# analog_pwr.net
KiCad netlist of a schematic drawn in Altium Designer
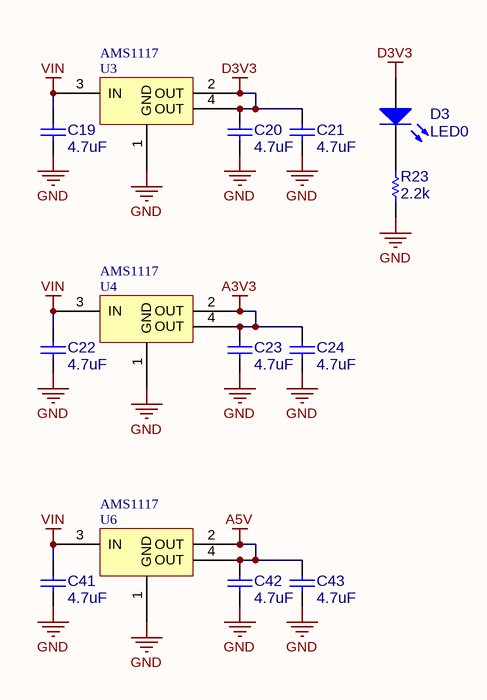
[diagram p0: analog_pwr.SchDoc]

(export (version "E")
  (design (tool "Eeschema 10.0.6"))
  (components
    (comp (ref "C19")
      (value "4.7uF")
      (footprint "TANT_B")
      (description "Capacitor")
      (fields (field (name "PUBLISHER") "Altium Limited"))
      (libsource (lib "Miscellaneous Devices") (part "Cap"))
    )
    (comp (ref "C20")
      (value "4.7uF")
      (footprint "C0603")
      (description "Capacitor")
      (fields (field (name "PUBLISHER") "Altium Limited"))
      (libsource (lib "Miscellaneous Devices") (part "Cap"))
    )
    (comp (ref "C21")
      (value "4.7uF")
      (footprint "TANT_B")
      (description "Capacitor")
      (fields (field (name "PUBLISHER") "Altium Limited"))
      (libsource (lib "Miscellaneous Devices") (part "Cap"))
    )
    (comp (ref "C22")
      (value "4.7uF")
      (footprint "TANT_B")
      (description "Capacitor")
      (fields (field (name "PUBLISHER") "Altium Limited"))
      (libsource (lib "Miscellaneous Devices") (part "Cap"))
    )
    (comp (ref "C23")
      (value "4.7uF")
      (footprint "C0603")
      (description "Capacitor")
      (fields (field (name "PUBLISHER") "Altium Limited"))
      (libsource (lib "Miscellaneous Devices") (part "Cap"))
    )
    (comp (ref "C24")
      (value "4.7uF")
      (footprint "TANT_B")
      (description "Capacitor")
      (fields (field (name "PUBLISHER") "Altium Limited"))
      (libsource (lib "Miscellaneous Devices") (part "Cap"))
    )
    (comp (ref "C41")
      (value "4.7uF")
      (footprint "TANT_B")
      (description "Capacitor")
      (fields (field (name "PUBLISHER") "Altium Limited"))
      (libsource (lib "Miscellaneous Devices") (part "Cap"))
    )
    (comp (ref "C42")
      (value "4.7uF")
      (footprint "C0603")
      (description "Capacitor")
      (fields (field (name "PUBLISHER") "Altium Limited"))
      (libsource (lib "Miscellaneous Devices") (part "Cap"))
    )
    (comp (ref "C43")
      (value "4.7uF")
      (footprint "TANT_B")
      (description "Capacitor")
      (fields (field (name "PUBLISHER") "Altium Limited"))
      (libsource (lib "Miscellaneous Devices") (part "Cap"))
    )
    (comp (ref "D3")
      (value "LED0")
      (footprint "LED0603")
      (description "Typical INFRARED GaAs LED")
      (fields (field (name "PUBLISHER") "Altium Limited"))
      (libsource (lib "Miscellaneous Devices") (part "LED0"))
    )
    (comp (ref "R23")
      (value "2.2k")
      (footprint "R0603")
      (description "Resistor")
      (fields (field (name "PUBLISHER") "Altium Limited"))
      (libsource (lib "Miscellaneous Devices") (part "Res1"))
    )
    (comp (ref "U3")
      (value "AMS1117")
      (footprint "SOT223")
      (libsource (lib "ADI-MEMs-more") (part "AMS1117"))
    )
    (comp (ref "U4")
      (value "AMS1117")
      (footprint "SOT223")
      (libsource (lib "ADI-MEMs-more") (part "AMS1117"))
    )
    (comp (ref "U6")
      (value "AMS1117")
      (footprint "SOT223")
      (libsource (lib "ADI-MEMs-more") (part "AMS1117"))
    )
  )
  (nets
    (net (code "1") (name "A3V3") (class "Default")
      (node (ref "C23") (pin "1") (pinfunction "1_1") (pintype "passive"))
      (node (ref "C24") (pin "1") (pinfunction "1_1") (pintype "passive"))
      (node (ref "U4") (pin "2") (pinfunction "OUT_2") (pintype "passive"))
      (node (ref "U4") (pin "4") (pinfunction "OUT_4") (pintype "passive"))
    )
    (net (code "2") (name "A5V") (class "Default")
      (node (ref "C42") (pin "1") (pinfunction "1_1") (pintype "passive"))
      (node (ref "C43") (pin "1") (pinfunction "1_1") (pintype "passive"))
      (node (ref "U6") (pin "2") (pinfunction "OUT_2") (pintype "passive"))
      (node (ref "U6") (pin "4") (pinfunction "OUT_4") (pintype "passive"))
    )
    (net (code "3") (name "D3V3") (class "Default")
      (node (ref "C20") (pin "1") (pinfunction "1_1") (pintype "passive"))
      (node (ref "C21") (pin "1") (pinfunction "1_1") (pintype "passive"))
      (node (ref "D3") (pin "1") (pinfunction "A_1") (pintype "passive"))
      (node (ref "U3") (pin "2") (pinfunction "OUT_2") (pintype "passive"))
      (node (ref "U3") (pin "4") (pinfunction "OUT_4") (pintype "passive"))
    )
    (net (code "4") (name "GND") (class "Default")
      (node (ref "C19") (pin "2") (pinfunction "2_2") (pintype "passive"))
      (node (ref "C20") (pin "2") (pinfunction "2_2") (pintype "passive"))
      (node (ref "C21") (pin "2") (pinfunction "2_2") (pintype "passive"))
      (node (ref "C22") (pin "2") (pinfunction "2_2") (pintype "passive"))
      (node (ref "C23") (pin "2") (pinfunction "2_2") (pintype "passive"))
      (node (ref "C24") (pin "2") (pinfunction "2_2") (pintype "passive"))
      (node (ref "C41") (pin "2") (pinfunction "2_2") (pintype "passive"))
      (node (ref "C42") (pin "2") (pinfunction "2_2") (pintype "passive"))
      (node (ref "C43") (pin "2") (pinfunction "2_2") (pintype "passive"))
      (node (ref "R23") (pin "1") (pinfunction "1_1") (pintype "passive"))
      (node (ref "U3") (pin "1") (pinfunction "GND_1") (pintype "passive"))
      (node (ref "U4") (pin "1") (pinfunction "GND_1") (pintype "passive"))
      (node (ref "U6") (pin "1") (pinfunction "GND_1") (pintype "passive"))
    )
    (net (code "5") (name "Net-(D3-K)") (class "Default")
      (node (ref "D3") (pin "2") (pinfunction "K_2") (pintype "passive"))
      (node (ref "R23") (pin "2") (pinfunction "2_2") (pintype "passive"))
    )
    (net (code "6") (name "VIN") (class "Default")
      (node (ref "C19") (pin "1") (pinfunction "1_1") (pintype "passive"))
      (node (ref "C22") (pin "1") (pinfunction "1_1") (pintype "passive"))
      (node (ref "C41") (pin "1") (pinfunction "1_1") (pintype "passive"))
      (node (ref "U3") (pin "3") (pinfunction "IN_3") (pintype "passive"))
      (node (ref "U4") (pin "3") (pinfunction "IN_3") (pintype "passive"))
      (node (ref "U6") (pin "3") (pinfunction "IN_3") (pintype "passive"))
    )
  )
)
